# ram-8x2K.net
KiCad netlist of a schematic drawn in EAGLE
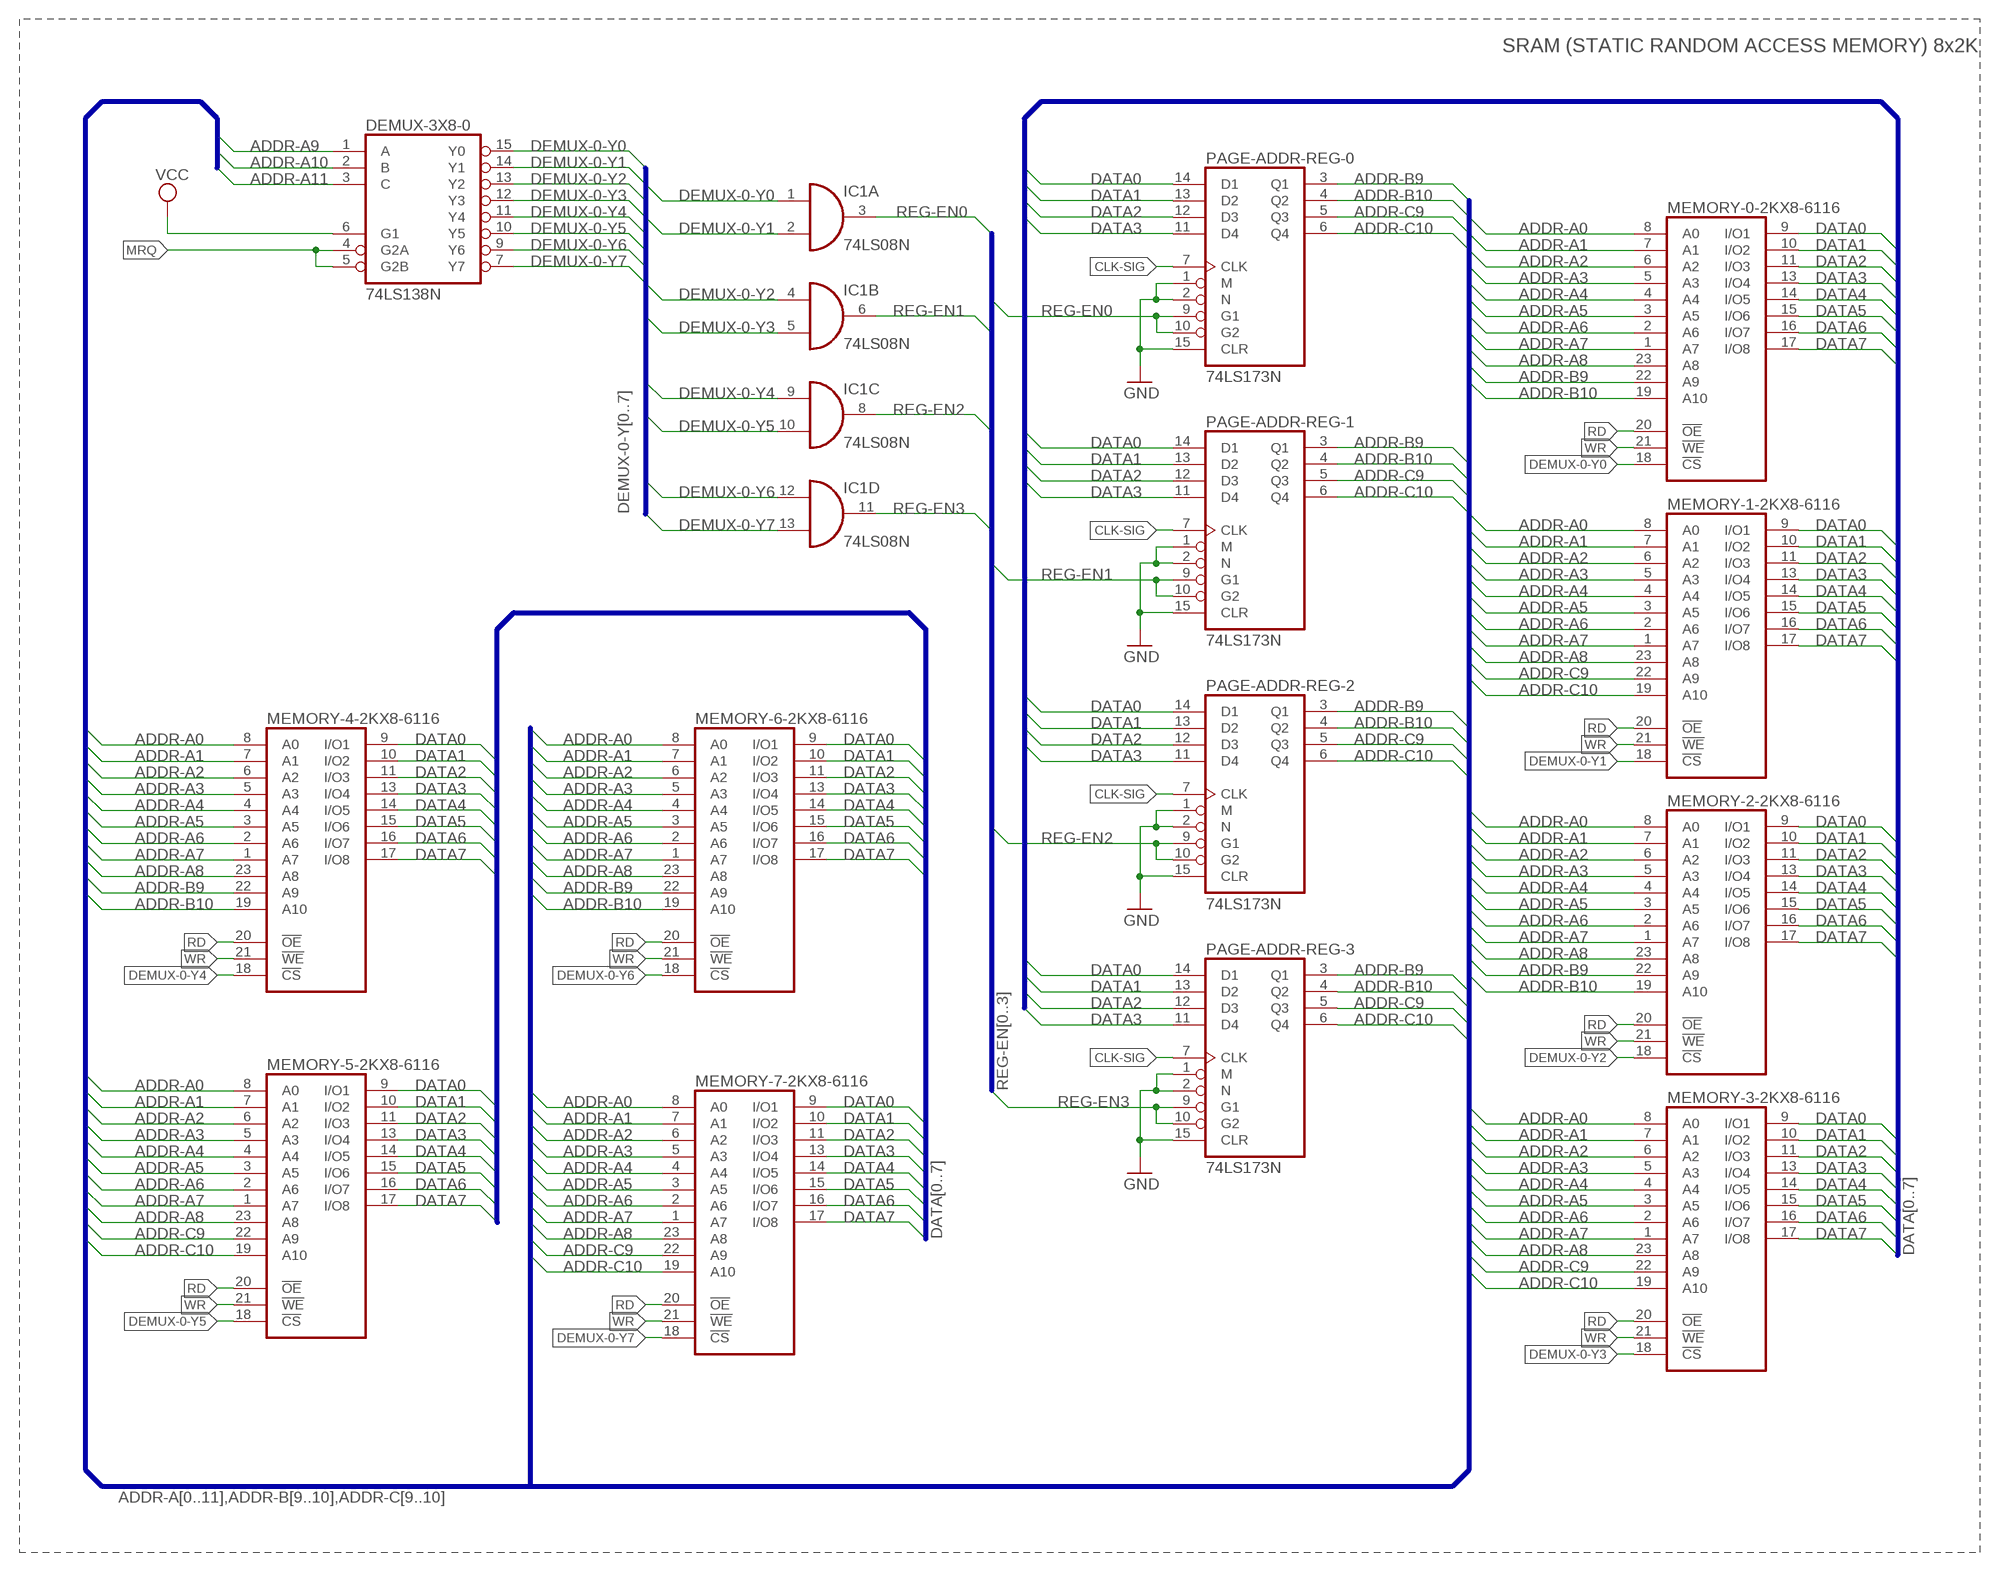
[diagram p0: schematic, sheet 1]

(export (version "E")
  (design (tool "Eeschema 10.0.6"))
  (components
    (comp (ref "DEMUX-3X8-0")
      (value "74LS138N")
      (footprint "eagle-import:DIL16")
      (libsource (lib "eagle-import") (part "74138NLS"))
    )
    (comp (ref "IC1")
      (value "74LS08N")
      (footprint "eagle-import:DIL14")
      (libsource (lib "eagle-import") (part "7408NLS"))
    )
    (comp (ref "MEMORY-0-2KX8-6116")
      (value "6116P")
      (footprint "eagle-import:DIL24-6")
      (libsource (lib "eagle-import") (part "6116P"))
    )
    (comp (ref "MEMORY-1-2KX8-6116")
      (value "6116P")
      (footprint "eagle-import:DIL24-6")
      (libsource (lib "eagle-import") (part "6116P"))
    )
    (comp (ref "MEMORY-2-2KX8-6116")
      (value "6116P")
      (footprint "eagle-import:DIL24-6")
      (libsource (lib "eagle-import") (part "6116P"))
    )
    (comp (ref "MEMORY-3-2KX8-6116")
      (value "6116P")
      (footprint "eagle-import:DIL24-6")
      (libsource (lib "eagle-import") (part "6116P"))
    )
    (comp (ref "MEMORY-4-2KX8-6116")
      (value "6116P")
      (footprint "eagle-import:DIL24-6")
      (libsource (lib "eagle-import") (part "6116P"))
    )
    (comp (ref "MEMORY-5-2KX8-6116")
      (value "6116P")
      (footprint "eagle-import:DIL24-6")
      (libsource (lib "eagle-import") (part "6116P"))
    )
    (comp (ref "MEMORY-6-2KX8-6116")
      (value "6116P")
      (footprint "eagle-import:DIL24-6")
      (libsource (lib "eagle-import") (part "6116P"))
    )
    (comp (ref "MEMORY-7-2KX8-6116")
      (value "6116P")
      (footprint "eagle-import:DIL24-6")
      (libsource (lib "eagle-import") (part "6116P"))
    )
    (comp (ref "PAGE-ADDR-REG-0")
      (value "74LS173N")
      (footprint "eagle-import:DIL16")
      (libsource (lib "eagle-import") (part "74173NLS"))
    )
    (comp (ref "PAGE-ADDR-REG-1")
      (value "74LS173N")
      (footprint "eagle-import:DIL16")
      (libsource (lib "eagle-import") (part "74173NLS"))
    )
    (comp (ref "PAGE-ADDR-REG-2")
      (value "74LS173N")
      (footprint "eagle-import:DIL16")
      (libsource (lib "eagle-import") (part "74173NLS"))
    )
    (comp (ref "PAGE-ADDR-REG-3")
      (value "74LS173N")
      (footprint "eagle-import:DIL16")
      (libsource (lib "eagle-import") (part "74173NLS"))
    )
  )
  (nets
    (net (code "1") (name "/ADDR-A0") (class "Default")
      (node (ref "MEMORY-0-2KX8-6116") (pin "8") (pinfunction "A0_8") (pintype "input"))
      (node (ref "MEMORY-1-2KX8-6116") (pin "8") (pinfunction "A0_8") (pintype "input"))
      (node (ref "MEMORY-2-2KX8-6116") (pin "8") (pinfunction "A0_8") (pintype "input"))
      (node (ref "MEMORY-3-2KX8-6116") (pin "8") (pinfunction "A0_8") (pintype "input"))
      (node (ref "MEMORY-4-2KX8-6116") (pin "8") (pinfunction "A0_8") (pintype "input"))
      (node (ref "MEMORY-5-2KX8-6116") (pin "8") (pinfunction "A0_8") (pintype "input"))
      (node (ref "MEMORY-6-2KX8-6116") (pin "8") (pinfunction "A0_8") (pintype "input"))
      (node (ref "MEMORY-7-2KX8-6116") (pin "8") (pinfunction "A0_8") (pintype "input"))
    )
    (net (code "2") (name "/ADDR-A1") (class "Default")
      (node (ref "MEMORY-0-2KX8-6116") (pin "7") (pinfunction "A1_7") (pintype "input"))
      (node (ref "MEMORY-1-2KX8-6116") (pin "7") (pinfunction "A1_7") (pintype "input"))
      (node (ref "MEMORY-2-2KX8-6116") (pin "7") (pinfunction "A1_7") (pintype "input"))
      (node (ref "MEMORY-3-2KX8-6116") (pin "7") (pinfunction "A1_7") (pintype "input"))
      (node (ref "MEMORY-4-2KX8-6116") (pin "7") (pinfunction "A1_7") (pintype "input"))
      (node (ref "MEMORY-5-2KX8-6116") (pin "7") (pinfunction "A1_7") (pintype "input"))
      (node (ref "MEMORY-6-2KX8-6116") (pin "7") (pinfunction "A1_7") (pintype "input"))
      (node (ref "MEMORY-7-2KX8-6116") (pin "7") (pinfunction "A1_7") (pintype "input"))
    )
    (net (code "3") (name "/ADDR-A2") (class "Default")
      (node (ref "MEMORY-0-2KX8-6116") (pin "6") (pinfunction "A2_6") (pintype "input"))
      (node (ref "MEMORY-1-2KX8-6116") (pin "6") (pinfunction "A2_6") (pintype "input"))
      (node (ref "MEMORY-2-2KX8-6116") (pin "6") (pinfunction "A2_6") (pintype "input"))
      (node (ref "MEMORY-3-2KX8-6116") (pin "6") (pinfunction "A2_6") (pintype "input"))
      (node (ref "MEMORY-4-2KX8-6116") (pin "6") (pinfunction "A2_6") (pintype "input"))
      (node (ref "MEMORY-5-2KX8-6116") (pin "6") (pinfunction "A2_6") (pintype "input"))
      (node (ref "MEMORY-6-2KX8-6116") (pin "6") (pinfunction "A2_6") (pintype "input"))
      (node (ref "MEMORY-7-2KX8-6116") (pin "6") (pinfunction "A2_6") (pintype "input"))
    )
    (net (code "4") (name "/ADDR-A3") (class "Default")
      (node (ref "MEMORY-0-2KX8-6116") (pin "5") (pinfunction "A3_5") (pintype "input"))
      (node (ref "MEMORY-1-2KX8-6116") (pin "5") (pinfunction "A3_5") (pintype "input"))
      (node (ref "MEMORY-2-2KX8-6116") (pin "5") (pinfunction "A3_5") (pintype "input"))
      (node (ref "MEMORY-3-2KX8-6116") (pin "5") (pinfunction "A3_5") (pintype "input"))
      (node (ref "MEMORY-4-2KX8-6116") (pin "5") (pinfunction "A3_5") (pintype "input"))
      (node (ref "MEMORY-5-2KX8-6116") (pin "5") (pinfunction "A3_5") (pintype "input"))
      (node (ref "MEMORY-6-2KX8-6116") (pin "5") (pinfunction "A3_5") (pintype "input"))
      (node (ref "MEMORY-7-2KX8-6116") (pin "5") (pinfunction "A3_5") (pintype "input"))
    )
    (net (code "5") (name "/ADDR-A4") (class "Default")
      (node (ref "MEMORY-0-2KX8-6116") (pin "4") (pinfunction "A4_4") (pintype "input"))
      (node (ref "MEMORY-1-2KX8-6116") (pin "4") (pinfunction "A4_4") (pintype "input"))
      (node (ref "MEMORY-2-2KX8-6116") (pin "4") (pinfunction "A4_4") (pintype "input"))
      (node (ref "MEMORY-3-2KX8-6116") (pin "4") (pinfunction "A4_4") (pintype "input"))
      (node (ref "MEMORY-4-2KX8-6116") (pin "4") (pinfunction "A4_4") (pintype "input"))
      (node (ref "MEMORY-5-2KX8-6116") (pin "4") (pinfunction "A4_4") (pintype "input"))
      (node (ref "MEMORY-6-2KX8-6116") (pin "4") (pinfunction "A4_4") (pintype "input"))
      (node (ref "MEMORY-7-2KX8-6116") (pin "4") (pinfunction "A4_4") (pintype "input"))
    )
    (net (code "6") (name "/ADDR-A5") (class "Default")
      (node (ref "MEMORY-0-2KX8-6116") (pin "3") (pinfunction "A5_3") (pintype "input"))
      (node (ref "MEMORY-1-2KX8-6116") (pin "3") (pinfunction "A5_3") (pintype "input"))
      (node (ref "MEMORY-2-2KX8-6116") (pin "3") (pinfunction "A5_3") (pintype "input"))
      (node (ref "MEMORY-3-2KX8-6116") (pin "3") (pinfunction "A5_3") (pintype "input"))
      (node (ref "MEMORY-4-2KX8-6116") (pin "3") (pinfunction "A5_3") (pintype "input"))
      (node (ref "MEMORY-5-2KX8-6116") (pin "3") (pinfunction "A5_3") (pintype "input"))
      (node (ref "MEMORY-6-2KX8-6116") (pin "3") (pinfunction "A5_3") (pintype "input"))
      (node (ref "MEMORY-7-2KX8-6116") (pin "3") (pinfunction "A5_3") (pintype "input"))
    )
    (net (code "7") (name "/ADDR-A6") (class "Default")
      (node (ref "MEMORY-0-2KX8-6116") (pin "2") (pinfunction "A6_2") (pintype "input"))
      (node (ref "MEMORY-1-2KX8-6116") (pin "2") (pinfunction "A6_2") (pintype "input"))
      (node (ref "MEMORY-2-2KX8-6116") (pin "2") (pinfunction "A6_2") (pintype "input"))
      (node (ref "MEMORY-3-2KX8-6116") (pin "2") (pinfunction "A6_2") (pintype "input"))
      (node (ref "MEMORY-4-2KX8-6116") (pin "2") (pinfunction "A6_2") (pintype "input"))
      (node (ref "MEMORY-5-2KX8-6116") (pin "2") (pinfunction "A6_2") (pintype "input"))
      (node (ref "MEMORY-6-2KX8-6116") (pin "2") (pinfunction "A6_2") (pintype "input"))
      (node (ref "MEMORY-7-2KX8-6116") (pin "2") (pinfunction "A6_2") (pintype "input"))
    )
    (net (code "8") (name "/ADDR-A7") (class "Default")
      (node (ref "MEMORY-0-2KX8-6116") (pin "1") (pinfunction "A7_1") (pintype "input"))
      (node (ref "MEMORY-1-2KX8-6116") (pin "1") (pinfunction "A7_1") (pintype "input"))
      (node (ref "MEMORY-2-2KX8-6116") (pin "1") (pinfunction "A7_1") (pintype "input"))
      (node (ref "MEMORY-3-2KX8-6116") (pin "1") (pinfunction "A7_1") (pintype "input"))
      (node (ref "MEMORY-4-2KX8-6116") (pin "1") (pinfunction "A7_1") (pintype "input"))
      (node (ref "MEMORY-5-2KX8-6116") (pin "1") (pinfunction "A7_1") (pintype "input"))
      (node (ref "MEMORY-6-2KX8-6116") (pin "1") (pinfunction "A7_1") (pintype "input"))
      (node (ref "MEMORY-7-2KX8-6116") (pin "1") (pinfunction "A7_1") (pintype "input"))
    )
    (net (code "9") (name "/ADDR-A8") (class "Default")
      (node (ref "MEMORY-0-2KX8-6116") (pin "23") (pinfunction "A8_23") (pintype "input"))
      (node (ref "MEMORY-1-2KX8-6116") (pin "23") (pinfunction "A8_23") (pintype "input"))
      (node (ref "MEMORY-2-2KX8-6116") (pin "23") (pinfunction "A8_23") (pintype "input"))
      (node (ref "MEMORY-3-2KX8-6116") (pin "23") (pinfunction "A8_23") (pintype "input"))
      (node (ref "MEMORY-4-2KX8-6116") (pin "23") (pinfunction "A8_23") (pintype "input"))
      (node (ref "MEMORY-5-2KX8-6116") (pin "23") (pinfunction "A8_23") (pintype "input"))
      (node (ref "MEMORY-6-2KX8-6116") (pin "23") (pinfunction "A8_23") (pintype "input"))
      (node (ref "MEMORY-7-2KX8-6116") (pin "23") (pinfunction "A8_23") (pintype "input"))
    )
    (net (code "10") (name "/ADDR-A9") (class "Default")
      (node (ref "DEMUX-3X8-0") (pin "1") (pinfunction "A_1") (pintype "input"))
    )
    (net (code "11") (name "/ADDR-A10") (class "Default")
      (node (ref "DEMUX-3X8-0") (pin "2") (pinfunction "B_2") (pintype "input"))
    )
    (net (code "12") (name "/ADDR-A11") (class "Default")
      (node (ref "DEMUX-3X8-0") (pin "3") (pinfunction "C_3") (pintype "input"))
    )
    (net (code "13") (name "/ADDR-B9") (class "Default")
      (node (ref "MEMORY-0-2KX8-6116") (pin "22") (pinfunction "A9_22") (pintype "input"))
      (node (ref "MEMORY-2-2KX8-6116") (pin "22") (pinfunction "A9_22") (pintype "input"))
      (node (ref "MEMORY-4-2KX8-6116") (pin "22") (pinfunction "A9_22") (pintype "input"))
      (node (ref "MEMORY-6-2KX8-6116") (pin "22") (pinfunction "A9_22") (pintype "input"))
      (node (ref "PAGE-ADDR-REG-0") (pin "3") (pinfunction "Q1_3") (pintype "tri_state"))
      (node (ref "PAGE-ADDR-REG-1") (pin "3") (pinfunction "Q1_3") (pintype "tri_state"))
      (node (ref "PAGE-ADDR-REG-2") (pin "3") (pinfunction "Q1_3") (pintype "tri_state"))
      (node (ref "PAGE-ADDR-REG-3") (pin "3") (pinfunction "Q1_3") (pintype "tri_state"))
    )
    (net (code "14") (name "/ADDR-B10") (class "Default")
      (node (ref "MEMORY-0-2KX8-6116") (pin "19") (pinfunction "A10_19") (pintype "input"))
      (node (ref "MEMORY-2-2KX8-6116") (pin "19") (pinfunction "A10_19") (pintype "input"))
      (node (ref "MEMORY-4-2KX8-6116") (pin "19") (pinfunction "A10_19") (pintype "input"))
      (node (ref "MEMORY-6-2KX8-6116") (pin "19") (pinfunction "A10_19") (pintype "input"))
      (node (ref "PAGE-ADDR-REG-0") (pin "4") (pinfunction "Q2_4") (pintype "tri_state"))
      (node (ref "PAGE-ADDR-REG-1") (pin "4") (pinfunction "Q2_4") (pintype "tri_state"))
      (node (ref "PAGE-ADDR-REG-2") (pin "4") (pinfunction "Q2_4") (pintype "tri_state"))
      (node (ref "PAGE-ADDR-REG-3") (pin "4") (pinfunction "Q2_4") (pintype "tri_state"))
    )
    (net (code "15") (name "/ADDR-C9") (class "Default")
      (node (ref "MEMORY-1-2KX8-6116") (pin "22") (pinfunction "A9_22") (pintype "input"))
      (node (ref "MEMORY-3-2KX8-6116") (pin "22") (pinfunction "A9_22") (pintype "input"))
      (node (ref "MEMORY-5-2KX8-6116") (pin "22") (pinfunction "A9_22") (pintype "input"))
      (node (ref "MEMORY-7-2KX8-6116") (pin "22") (pinfunction "A9_22") (pintype "input"))
      (node (ref "PAGE-ADDR-REG-0") (pin "5") (pinfunction "Q3_5") (pintype "tri_state"))
      (node (ref "PAGE-ADDR-REG-1") (pin "5") (pinfunction "Q3_5") (pintype "tri_state"))
      (node (ref "PAGE-ADDR-REG-2") (pin "5") (pinfunction "Q3_5") (pintype "tri_state"))
      (node (ref "PAGE-ADDR-REG-3") (pin "5") (pinfunction "Q3_5") (pintype "tri_state"))
    )
    (net (code "16") (name "/ADDR-C10") (class "Default")
      (node (ref "MEMORY-1-2KX8-6116") (pin "19") (pinfunction "A10_19") (pintype "input"))
      (node (ref "MEMORY-3-2KX8-6116") (pin "19") (pinfunction "A10_19") (pintype "input"))
      (node (ref "MEMORY-5-2KX8-6116") (pin "19") (pinfunction "A10_19") (pintype "input"))
      (node (ref "MEMORY-7-2KX8-6116") (pin "19") (pinfunction "A10_19") (pintype "input"))
      (node (ref "PAGE-ADDR-REG-0") (pin "6") (pinfunction "Q4_6") (pintype "tri_state"))
      (node (ref "PAGE-ADDR-REG-1") (pin "6") (pinfunction "Q4_6") (pintype "tri_state"))
      (node (ref "PAGE-ADDR-REG-2") (pin "6") (pinfunction "Q4_6") (pintype "tri_state"))
      (node (ref "PAGE-ADDR-REG-3") (pin "6") (pinfunction "Q4_6") (pintype "tri_state"))
    )
    (net (code "17") (name "/DATA0") (class "Default")
      (node (ref "MEMORY-0-2KX8-6116") (pin "9") (pinfunction "I/O1_9") (pintype "bidirectional"))
      (node (ref "MEMORY-1-2KX8-6116") (pin "9") (pinfunction "I/O1_9") (pintype "bidirectional"))
      (node (ref "MEMORY-2-2KX8-6116") (pin "9") (pinfunction "I/O1_9") (pintype "bidirectional"))
      (node (ref "MEMORY-3-2KX8-6116") (pin "9") (pinfunction "I/O1_9") (pintype "bidirectional"))
      (node (ref "MEMORY-4-2KX8-6116") (pin "9") (pinfunction "I/O1_9") (pintype "bidirectional"))
      (node (ref "MEMORY-5-2KX8-6116") (pin "9") (pinfunction "I/O1_9") (pintype "bidirectional"))
      (node (ref "MEMORY-6-2KX8-6116") (pin "9") (pinfunction "I/O1_9") (pintype "bidirectional"))
      (node (ref "MEMORY-7-2KX8-6116") (pin "9") (pinfunction "I/O1_9") (pintype "bidirectional"))
      (node (ref "PAGE-ADDR-REG-0") (pin "14") (pinfunction "D1_14") (pintype "input"))
      (node (ref "PAGE-ADDR-REG-1") (pin "14") (pinfunction "D1_14") (pintype "input"))
      (node (ref "PAGE-ADDR-REG-2") (pin "14") (pinfunction "D1_14") (pintype "input"))
      (node (ref "PAGE-ADDR-REG-3") (pin "14") (pinfunction "D1_14") (pintype "input"))
    )
    (net (code "18") (name "/DATA1") (class "Default")
      (node (ref "MEMORY-0-2KX8-6116") (pin "10") (pinfunction "I/O2_10") (pintype "bidirectional"))
      (node (ref "MEMORY-1-2KX8-6116") (pin "10") (pinfunction "I/O2_10") (pintype "bidirectional"))
      (node (ref "MEMORY-2-2KX8-6116") (pin "10") (pinfunction "I/O2_10") (pintype "bidirectional"))
      (node (ref "MEMORY-3-2KX8-6116") (pin "10") (pinfunction "I/O2_10") (pintype "bidirectional"))
      (node (ref "MEMORY-4-2KX8-6116") (pin "10") (pinfunction "I/O2_10") (pintype "bidirectional"))
      (node (ref "MEMORY-5-2KX8-6116") (pin "10") (pinfunction "I/O2_10") (pintype "bidirectional"))
      (node (ref "MEMORY-6-2KX8-6116") (pin "10") (pinfunction "I/O2_10") (pintype "bidirectional"))
      (node (ref "MEMORY-7-2KX8-6116") (pin "10") (pinfunction "I/O2_10") (pintype "bidirectional"))
      (node (ref "PAGE-ADDR-REG-0") (pin "13") (pinfunction "D2_13") (pintype "input"))
      (node (ref "PAGE-ADDR-REG-1") (pin "13") (pinfunction "D2_13") (pintype "input"))
      (node (ref "PAGE-ADDR-REG-2") (pin "13") (pinfunction "D2_13") (pintype "input"))
      (node (ref "PAGE-ADDR-REG-3") (pin "13") (pinfunction "D2_13") (pintype "input"))
    )
    (net (code "19") (name "/DATA2") (class "Default")
      (node (ref "MEMORY-0-2KX8-6116") (pin "11") (pinfunction "I/O3_11") (pintype "bidirectional"))
      (node (ref "MEMORY-1-2KX8-6116") (pin "11") (pinfunction "I/O3_11") (pintype "bidirectional"))
      (node (ref "MEMORY-2-2KX8-6116") (pin "11") (pinfunction "I/O3_11") (pintype "bidirectional"))
      (node (ref "MEMORY-3-2KX8-6116") (pin "11") (pinfunction "I/O3_11") (pintype "bidirectional"))
      (node (ref "MEMORY-4-2KX8-6116") (pin "11") (pinfunction "I/O3_11") (pintype "bidirectional"))
      (node (ref "MEMORY-5-2KX8-6116") (pin "11") (pinfunction "I/O3_11") (pintype "bidirectional"))
      (node (ref "MEMORY-6-2KX8-6116") (pin "11") (pinfunction "I/O3_11") (pintype "bidirectional"))
      (node (ref "MEMORY-7-2KX8-6116") (pin "11") (pinfunction "I/O3_11") (pintype "bidirectional"))
      (node (ref "PAGE-ADDR-REG-0") (pin "12") (pinfunction "D3_12") (pintype "input"))
      (node (ref "PAGE-ADDR-REG-1") (pin "12") (pinfunction "D3_12") (pintype "input"))
      (node (ref "PAGE-ADDR-REG-2") (pin "12") (pinfunction "D3_12") (pintype "input"))
      (node (ref "PAGE-ADDR-REG-3") (pin "12") (pinfunction "D3_12") (pintype "input"))
    )
    (net (code "20") (name "/DATA3") (class "Default")
      (node (ref "MEMORY-0-2KX8-6116") (pin "13") (pinfunction "I/O4_13") (pintype "bidirectional"))
      (node (ref "MEMORY-1-2KX8-6116") (pin "13") (pinfunction "I/O4_13") (pintype "bidirectional"))
      (node (ref "MEMORY-2-2KX8-6116") (pin "13") (pinfunction "I/O4_13") (pintype "bidirectional"))
      (node (ref "MEMORY-3-2KX8-6116") (pin "13") (pinfunction "I/O4_13") (pintype "bidirectional"))
      (node (ref "MEMORY-4-2KX8-6116") (pin "13") (pinfunction "I/O4_13") (pintype "bidirectional"))
      (node (ref "MEMORY-5-2KX8-6116") (pin "13") (pinfunction "I/O4_13") (pintype "bidirectional"))
      (node (ref "MEMORY-6-2KX8-6116") (pin "13") (pinfunction "I/O4_13") (pintype "bidirectional"))
      (node (ref "MEMORY-7-2KX8-6116") (pin "13") (pinfunction "I/O4_13") (pintype "bidirectional"))
      (node (ref "PAGE-ADDR-REG-0") (pin "11") (pinfunction "D4_11") (pintype "input"))
      (node (ref "PAGE-ADDR-REG-1") (pin "11") (pinfunction "D4_11") (pintype "input"))
      (node (ref "PAGE-ADDR-REG-2") (pin "11") (pinfunction "D4_11") (pintype "input"))
      (node (ref "PAGE-ADDR-REG-3") (pin "11") (pinfunction "D4_11") (pintype "input"))
    )
    (net (code "21") (name "/DATA4") (class "Default")
      (node (ref "MEMORY-0-2KX8-6116") (pin "14") (pinfunction "I/O5_14") (pintype "bidirectional"))
      (node (ref "MEMORY-1-2KX8-6116") (pin "14") (pinfunction "I/O5_14") (pintype "bidirectional"))
      (node (ref "MEMORY-2-2KX8-6116") (pin "14") (pinfunction "I/O5_14") (pintype "bidirectional"))
      (node (ref "MEMORY-3-2KX8-6116") (pin "14") (pinfunction "I/O5_14") (pintype "bidirectional"))
      (node (ref "MEMORY-4-2KX8-6116") (pin "14") (pinfunction "I/O5_14") (pintype "bidirectional"))
      (node (ref "MEMORY-5-2KX8-6116") (pin "14") (pinfunction "I/O5_14") (pintype "bidirectional"))
      (node (ref "MEMORY-6-2KX8-6116") (pin "14") (pinfunction "I/O5_14") (pintype "bidirectional"))
      (node (ref "MEMORY-7-2KX8-6116") (pin "14") (pinfunction "I/O5_14") (pintype "bidirectional"))
    )
    (net (code "22") (name "/DATA5") (class "Default")
      (node (ref "MEMORY-0-2KX8-6116") (pin "15") (pinfunction "I/O6_15") (pintype "bidirectional"))
      (node (ref "MEMORY-1-2KX8-6116") (pin "15") (pinfunction "I/O6_15") (pintype "bidirectional"))
      (node (ref "MEMORY-2-2KX8-6116") (pin "15") (pinfunction "I/O6_15") (pintype "bidirectional"))
      (node (ref "MEMORY-3-2KX8-6116") (pin "15") (pinfunction "I/O6_15") (pintype "bidirectional"))
      (node (ref "MEMORY-4-2KX8-6116") (pin "15") (pinfunction "I/O6_15") (pintype "bidirectional"))
      (node (ref "MEMORY-5-2KX8-6116") (pin "15") (pinfunction "I/O6_15") (pintype "bidirectional"))
      (node (ref "MEMORY-6-2KX8-6116") (pin "15") (pinfunction "I/O6_15") (pintype "bidirectional"))
      (node (ref "MEMORY-7-2KX8-6116") (pin "15") (pinfunction "I/O6_15") (pintype "bidirectional"))
    )
    (net (code "23") (name "/DATA6") (class "Default")
      (node (ref "MEMORY-0-2KX8-6116") (pin "16") (pinfunction "I/O7_16") (pintype "bidirectional"))
      (node (ref "MEMORY-1-2KX8-6116") (pin "16") (pinfunction "I/O7_16") (pintype "bidirectional"))
      (node (ref "MEMORY-2-2KX8-6116") (pin "16") (pinfunction "I/O7_16") (pintype "bidirectional"))
      (node (ref "MEMORY-3-2KX8-6116") (pin "16") (pinfunction "I/O7_16") (pintype "bidirectional"))
      (node (ref "MEMORY-4-2KX8-6116") (pin "16") (pinfunction "I/O7_16") (pintype "bidirectional"))
      (node (ref "MEMORY-5-2KX8-6116") (pin "16") (pinfunction "I/O7_16") (pintype "bidirectional"))
      (node (ref "MEMORY-6-2KX8-6116") (pin "16") (pinfunction "I/O7_16") (pintype "bidirectional"))
      (node (ref "MEMORY-7-2KX8-6116") (pin "16") (pinfunction "I/O7_16") (pintype "bidirectional"))
    )
    (net (code "24") (name "/DATA7") (class "Default")
      (node (ref "MEMORY-0-2KX8-6116") (pin "17") (pinfunction "I/O8_17") (pintype "bidirectional"))
      (node (ref "MEMORY-1-2KX8-6116") (pin "17") (pinfunction "I/O8_17") (pintype "bidirectional"))
      (node (ref "MEMORY-2-2KX8-6116") (pin "17") (pinfunction "I/O8_17") (pintype "bidirectional"))
      (node (ref "MEMORY-3-2KX8-6116") (pin "17") (pinfunction "I/O8_17") (pintype "bidirectional"))
      (node (ref "MEMORY-4-2KX8-6116") (pin "17") (pinfunction "I/O8_17") (pintype "bidirectional"))
      (node (ref "MEMORY-5-2KX8-6116") (pin "17") (pinfunction "I/O8_17") (pintype "bidirectional"))
      (node (ref "MEMORY-6-2KX8-6116") (pin "17") (pinfunction "I/O8_17") (pintype "bidirectional"))
      (node (ref "MEMORY-7-2KX8-6116") (pin "17") (pinfunction "I/O8_17") (pintype "bidirectional"))
    )
    (net (code "27") (name "/REG-EN0") (class "Default")
      (node (ref "IC1") (pin "3") (pinfunction "O_3") (pintype "output"))
      (node (ref "PAGE-ADDR-REG-0") (pin "10") (pinfunction "G2_10") (pintype "input"))
      (node (ref "PAGE-ADDR-REG-0") (pin "9") (pinfunction "G1_9") (pintype "input"))
    )
    (net (code "28") (name "/REG-EN1") (class "Default")
      (node (ref "IC1") (pin "6") (pinfunction "O_6") (pintype "output"))
      (node (ref "PAGE-ADDR-REG-1") (pin "10") (pinfunction "G2_10") (pintype "input"))
      (node (ref "PAGE-ADDR-REG-1") (pin "9") (pinfunction "G1_9") (pintype "input"))
    )
    (net (code "29") (name "/REG-EN2") (class "Default")
      (node (ref "IC1") (pin "8") (pinfunction "O_8") (pintype "output"))
      (node (ref "PAGE-ADDR-REG-2") (pin "10") (pinfunction "G2_10") (pintype "input"))
      (node (ref "PAGE-ADDR-REG-2") (pin "9") (pinfunction "G1_9") (pintype "input"))
    )
    (net (code "30") (name "/REG-EN3") (class "Default")
      (node (ref "IC1") (pin "11") (pinfunction "O_11") (pintype "output"))
      (node (ref "PAGE-ADDR-REG-3") (pin "10") (pinfunction "G2_10") (pintype "input"))
      (node (ref "PAGE-ADDR-REG-3") (pin "9") (pinfunction "G1_9") (pintype "input"))
    )
    (net (code "32") (name "CLK-SIG") (class "Default")
      (node (ref "PAGE-ADDR-REG-0") (pin "7") (pinfunction "CLK_7") (pintype "input"))
      (node (ref "PAGE-ADDR-REG-1") (pin "7") (pinfunction "CLK_7") (pintype "input"))
      (node (ref "PAGE-ADDR-REG-2") (pin "7") (pinfunction "CLK_7") (pintype "input"))
      (node (ref "PAGE-ADDR-REG-3") (pin "7") (pinfunction "CLK_7") (pintype "input"))
    )
    (net (code "33") (name "DEMUX-0-Y0") (class "Default")
      (node (ref "DEMUX-3X8-0") (pin "15") (pinfunction "Y0_15") (pintype "output"))
      (node (ref "IC1") (pin "1") (pinfunction "I0_1") (pintype "input"))
      (node (ref "MEMORY-0-2KX8-6116") (pin "18") (pinfunction "~{CS}_18") (pintype "input"))
    )
    (net (code "34") (name "DEMUX-0-Y1") (class "Default")
      (node (ref "DEMUX-3X8-0") (pin "14") (pinfunction "Y1_14") (pintype "output"))
      (node (ref "IC1") (pin "2") (pinfunction "I1_2") (pintype "input"))
      (node (ref "MEMORY-1-2KX8-6116") (pin "18") (pinfunction "~{CS}_18") (pintype "input"))
    )
    (net (code "35") (name "DEMUX-0-Y2") (class "Default")
      (node (ref "DEMUX-3X8-0") (pin "13") (pinfunction "Y2_13") (pintype "output"))
      (node (ref "IC1") (pin "4") (pinfunction "I0_4") (pintype "input"))
      (node (ref "MEMORY-2-2KX8-6116") (pin "18") (pinfunction "~{CS}_18") (pintype "input"))
    )
    (net (code "36") (name "DEMUX-0-Y3") (class "Default")
      (node (ref "DEMUX-3X8-0") (pin "12") (pinfunction "Y3_12") (pintype "output"))
      (node (ref "IC1") (pin "5") (pinfunction "I1_5") (pintype "input"))
      (node (ref "MEMORY-3-2KX8-6116") (pin "18") (pinfunction "~{CS}_18") (pintype "input"))
    )
    (net (code "37") (name "DEMUX-0-Y4") (class "Default")
      (node (ref "DEMUX-3X8-0") (pin "11") (pinfunction "Y4_11") (pintype "output"))
      (node (ref "IC1") (pin "9") (pinfunction "I0_9") (pintype "input"))
      (node (ref "MEMORY-4-2KX8-6116") (pin "18") (pinfunction "~{CS}_18") (pintype "input"))
    )
    (net (code "38") (name "DEMUX-0-Y5") (class "Default")
      (node (ref "DEMUX-3X8-0") (pin "10") (pinfunction "Y5_10") (pintype "output"))
      (node (ref "IC1") (pin "10") (pinfunction "I1_10") (pintype "input"))
      (node (ref "MEMORY-5-2KX8-6116") (pin "18") (pinfunction "~{CS}_18") (pintype "input"))
    )
    (net (code "39") (name "DEMUX-0-Y6") (class "Default")
      (node (ref "DEMUX-3X8-0") (pin "9") (pinfunction "Y6_9") (pintype "output"))
      (node (ref "IC1") (pin "12") (pinfunction "I0_12") (pintype "input"))
      (node (ref "MEMORY-6-2KX8-6116") (pin "18") (pinfunction "~{CS}_18") (pintype "input"))
    )
    (net (code "40") (name "DEMUX-0-Y7") (class "Default")
      (node (ref "DEMUX-3X8-0") (pin "7") (pinfunction "Y7_7") (pintype "output"))
      (node (ref "IC1") (pin "13") (pinfunction "I1_13") (pintype "input"))
      (node (ref "MEMORY-7-2KX8-6116") (pin "18") (pinfunction "~{CS}_18") (pintype "input"))
    )
    (net (code "41") (name "GND") (class "Default")
      (node (ref "PAGE-ADDR-REG-0") (pin "1") (pinfunction "M_1") (pintype "input"))
      (node (ref "PAGE-ADDR-REG-0") (pin "15") (pinfunction "CLR_15") (pintype "input"))
      (node (ref "PAGE-ADDR-REG-0") (pin "2") (pinfunction "N_2") (pintype "input"))
      (node (ref "PAGE-ADDR-REG-1") (pin "1") (pinfunction "M_1") (pintype "input"))
      (node (ref "PAGE-ADDR-REG-1") (pin "15") (pinfunction "CLR_15") (pintype "input"))
      (node (ref "PAGE-ADDR-REG-1") (pin "2") (pinfunction "N_2") (pintype "input"))
      (node (ref "PAGE-ADDR-REG-2") (pin "1") (pinfunction "M_1") (pintype "input"))
      (node (ref "PAGE-ADDR-REG-2") (pin "15") (pinfunction "CLR_15") (pintype "input"))
      (node (ref "PAGE-ADDR-REG-2") (pin "2") (pinfunction "N_2") (pintype "input"))
      (node (ref "PAGE-ADDR-REG-3") (pin "1") (pinfunction "M_1") (pintype "input"))
      (node (ref "PAGE-ADDR-REG-3") (pin "15") (pinfunction "CLR_15") (pintype "input"))
      (node (ref "PAGE-ADDR-REG-3") (pin "2") (pinfunction "N_2") (pintype "input"))
    )
    (net (code "42") (name "MRQ") (class "Default")
      (node (ref "DEMUX-3X8-0") (pin "4") (pinfunction "G2A_4") (pintype "input"))
      (node (ref "DEMUX-3X8-0") (pin "5") (pinfunction "G2B_5") (pintype "input"))
    )
    (net (code "43") (name "RD") (class "Default")
      (node (ref "MEMORY-0-2KX8-6116") (pin "20") (pinfunction "~{OE}_20") (pintype "input"))
      (node (ref "MEMORY-1-2KX8-6116") (pin "20") (pinfunction "~{OE}_20") (pintype "input"))
      (node (ref "MEMORY-2-2KX8-6116") (pin "20") (pinfunction "~{OE}_20") (pintype "input"))
      (node (ref "MEMORY-3-2KX8-6116") (pin "20") (pinfunction "~{OE}_20") (pintype "input"))
      (node (ref "MEMORY-4-2KX8-6116") (pin "20") (pinfunction "~{OE}_20") (pintype "input"))
      (node (ref "MEMORY-5-2KX8-6116") (pin "20") (pinfunction "~{OE}_20") (pintype "input"))
      (node (ref "MEMORY-6-2KX8-6116") (pin "20") (pinfunction "~{OE}_20") (pintype "input"))
      (node (ref "MEMORY-7-2KX8-6116") (pin "20") (pinfunction "~{OE}_20") (pintype "input"))
    )
    (net (code "44") (name "VCC") (class "Default")
      (node (ref "DEMUX-3X8-0") (pin "6") (pinfunction "G1_6") (pintype "input"))
    )
    (net (code "45") (name "WR") (class "Default")
      (node (ref "MEMORY-0-2KX8-6116") (pin "21") (pinfunction "~{WE}_21") (pintype "input"))
      (node (ref "MEMORY-1-2KX8-6116") (pin "21") (pinfunction "~{WE}_21") (pintype "input"))
      (node (ref "MEMORY-2-2KX8-6116") (pin "21") (pinfunction "~{WE}_21") (pintype "input"))
      (node (ref "MEMORY-3-2KX8-6116") (pin "21") (pinfunction "~{WE}_21") (pintype "input"))
      (node (ref "MEMORY-4-2KX8-6116") (pin "21") (pinfunction "~{WE}_21") (pintype "input"))
      (node (ref "MEMORY-5-2KX8-6116") (pin "21") (pinfunction "~{WE}_21") (pintype "input"))
      (node (ref "MEMORY-6-2KX8-6116") (pin "21") (pinfunction "~{WE}_21") (pintype "input"))
      (node (ref "MEMORY-7-2KX8-6116") (pin "21") (pinfunction "~{WE}_21") (pintype "input"))
    )
  )
)
